# Pro_Co_RAT.net
KiCad netlist of a schematic drawn in Altium Designer
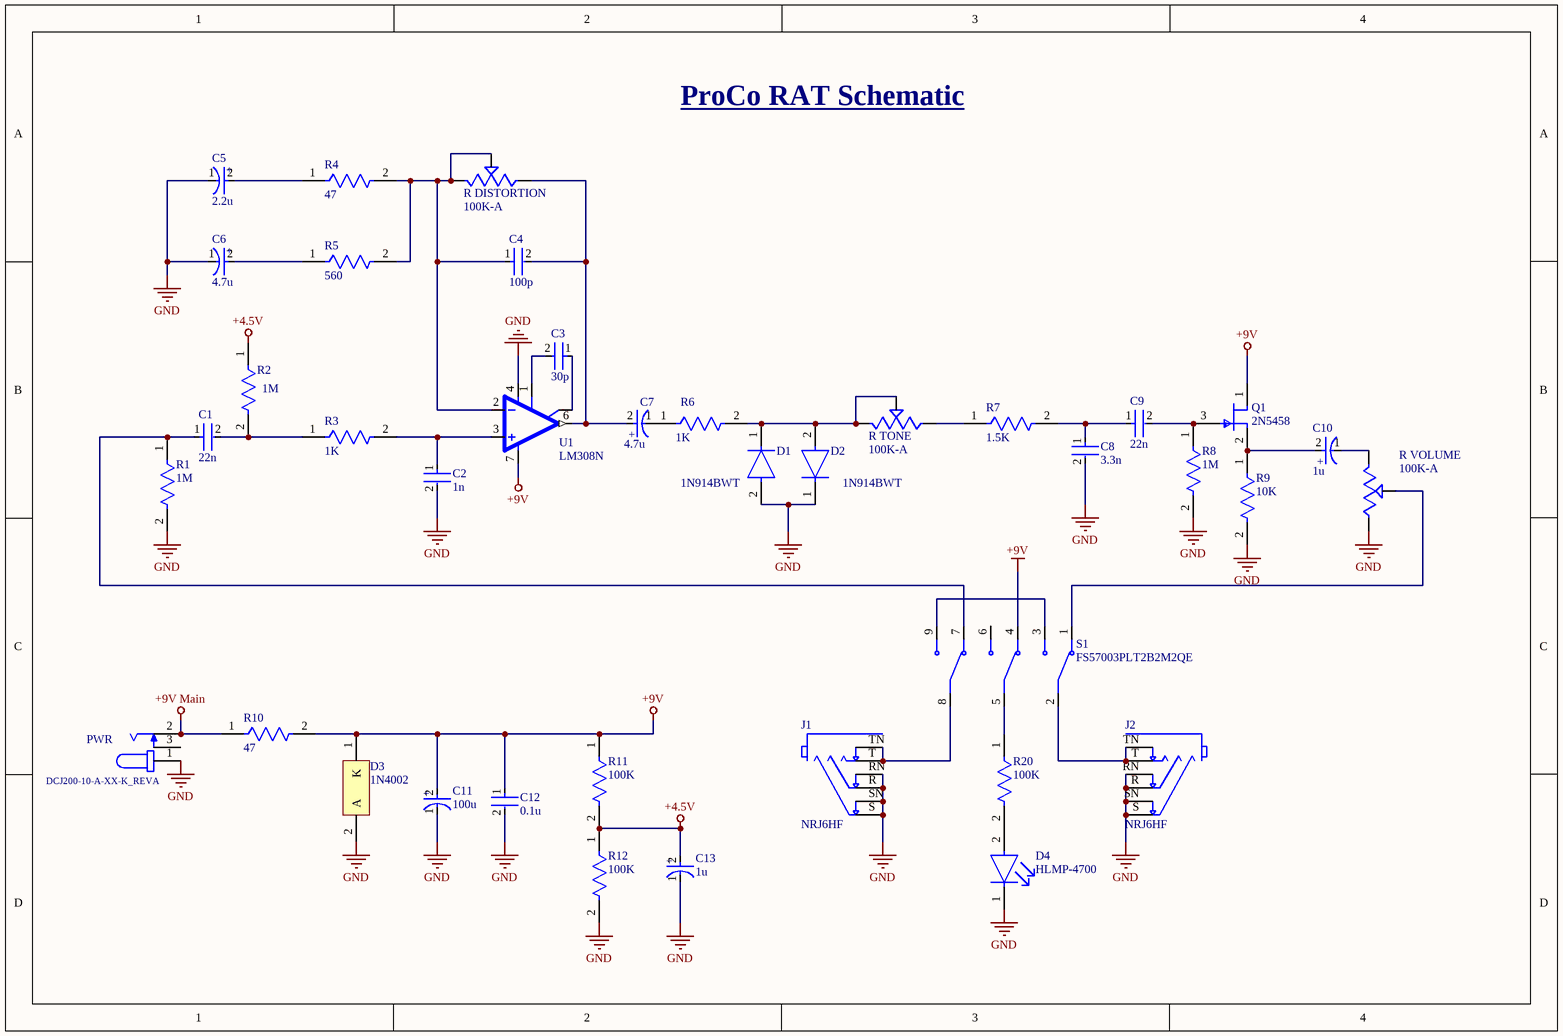
[diagram p0: Pro Co RAT.SchDoc]

(export (version "E")
  (design (tool "Eeschema 10.0.6"))
  (components
    (comp (ref "C1")
      (value "22n")
      (footprint "FP-VY2332M41Y5US63V7-MFG")
      (description "Capacitor Radiall")
      (fields (field (name "TOLERANCE") "20%"))
      (libsource (lib "Altium Content Vault") (part "11868f565c42a9108669ba33697ecf6"))
    )
    (comp (ref "C2")
      (value "1n")
      (footprint "FP-VY2332M41Y5US63V7-MFG")
      (description "Capacitor Radiall")
      (fields (field (name "TOLERANCE") "20%"))
      (libsource (lib "Altium Content Vault") (part "11868f565c42a9108669ba33697ecf6"))
    )
    (comp (ref "C3")
      (value "30p")
      (footprint "FP-VY2332M41Y5US63V7-MFG")
      (description "Capacitor Radiall")
      (fields (field (name "TOLERANCE") "20%"))
      (libsource (lib "Altium Content Vault") (part "11868f565c42a9108669ba33697ecf6"))
    )
    (comp (ref "C4")
      (value "100p")
      (footprint "FP-VY2332M41Y5US63V7-MFG")
      (description "Capacitor Radiall")
      (fields (field (name "TOLERANCE") "20%"))
      (libsource (lib "Altium Content Vault") (part "11868f565c42a9108669ba33697ecf6"))
    )
    (comp (ref "C5")
      (value "2.2u")
      (footprint "FP-RAD-TH-D_8_0_5-L_11_5-MFG")
      (description "Aluminum Electrolytic Capacitors (Radial Lead Type) 680uF ±20% 10V")
      (fields (field (name "TOLERANCE") "20%") (field (name "VOLTAGE") "10V"))
      (libsource (lib "Altium Content Vault") (part "a00bbbee19879c290e62620ae7e47b1"))
    )
    (comp (ref "C6")
      (value "4.7u")
      (footprint "FP-RAD-TH-D_8_0_5-L_11_5-MFG")
      (description "Aluminum Electrolytic Capacitors (Radial Lead Type) 680uF ±20% 10V")
      (fields (field (name "TOLERANCE") "20%") (field (name "VOLTAGE") "10V"))
      (libsource (lib "Altium Content Vault") (part "a00bbbee19879c290e62620ae7e47b1"))
    )
    (comp (ref "C7")
      (value "4.7u")
      (footprint "FP-RAD-TH-D_8_0_5-L_11_5-MFG")
      (description "Aluminum Electrolytic Capacitors (Radial Lead Type) 680uF ±20% 10V")
      (fields (field (name "TOLERANCE") "20%") (field (name "VOLTAGE") "10V"))
      (libsource (lib "Altium Content Vault") (part "a00bbbee19879c290e62620ae7e47b1"))
    )
    (comp (ref "C8")
      (value "3.3n")
      (footprint "FP-VY2332M41Y5US63V7-MFG")
      (description "Capacitor Radiall")
      (fields (field (name "TOLERANCE") "20%"))
      (libsource (lib "Altium Content Vault") (part "11868f565c42a9108669ba33697ecf6"))
    )
    (comp (ref "C9")
      (value "22n")
      (footprint "FP-VY2332M41Y5US63V7-MFG")
      (description "Capacitor Radiall")
      (fields (field (name "TOLERANCE") "20%"))
      (libsource (lib "Altium Content Vault") (part "11868f565c42a9108669ba33697ecf6"))
    )
    (comp (ref "C10")
      (value "1u")
      (footprint "FP-RAD-TH-D_8_0_5-L_11_5-MFG")
      (description "Aluminum Electrolytic Capacitors (Radial Lead Type) 680uF ±20% 10V")
      (fields (field (name "TOLERANCE") "20%") (field (name "VOLTAGE") "10V"))
      (libsource (lib "Altium Content Vault") (part "a00bbbee19879c290e62620ae7e47b1"))
    )
    (comp (ref "C11")
      (value "100u")
      (footprint "FP-RAD-TH-D_8_0_5-L_11_5-MFG")
      (description "Aluminum Electrolytic Capacitors (Radial Lead Type) 680uF ±20% 10V")
      (fields (field (name "TOLERANCE") "20%") (field (name "VOLTAGE") "10V"))
      (libsource (lib "Altium Content Vault") (part "a00bbbee19879c290e62620ae7e47b1"))
    )
    (comp (ref "C12")
      (value "0.1u")
      (footprint "FP-VY2332M41Y5US63V7-MFG")
      (description "Capacitor Radiall")
      (fields (field (name "TOLERANCE") "20%"))
      (libsource (lib "Altium Content Vault") (part "11868f565c42a9108669ba33697ecf6"))
    )
    (comp (ref "C13")
      (value "1u")
      (footprint "FP-RAD-TH-D_8_0_5-L_11_5-MFG")
      (description "Aluminum Electrolytic Capacitors (Radial Lead Type) 680uF ±20% 10V")
      (fields (field (name "TOLERANCE") "20%") (field (name "VOLTAGE") "10V"))
      (libsource (lib "Altium Content Vault") (part "a00bbbee19879c290e62620ae7e47b1"))
    )
    (comp (ref "D1")
      (value "1N914BWT")
      (footprint "FP-502-01-MFG")
      (description "DIODE GEN PURP 75V 200MA SOD523F")
      (fields
        (field (name "OCTOPART") "https://octopart.com/1n914bwt-on+semiconductor-84323166")
        (field (name "MANUFACTURER") "ON Semiconductor")
      )
      (libsource (lib "Altium Content Vault") (part "d7152d700b627762746794eb795d46e"))
    )
    (comp (ref "D2")
      (value "1N914BWT")
      (footprint "FP-502-01-MFG")
      (description "DIODE GEN PURP 75V 200MA SOD523F")
      (fields
        (field (name "OCTOPART") "https://octopart.com/1n914bwt-on+semiconductor-84323166")
        (field (name "MANUFACTURER") "ON Semiconductor")
      )
      (libsource (lib "Altium Content Vault") (part "d7152d700b627762746794eb795d46e"))
    )
    (comp (ref "D3")
      (value "1N4002")
      (footprint "ONSC-AXIAL_LEAD-2-59-10_P")
      (description "Standard Recovery Rectifier, 2-Pin Axial_Lead, Pb-Free, Bulk Bag")
      (fields (field (name "MANUFACTURER") "On Semiconductor"))
      (libsource (lib "Altium Content Vault") (part "ONSC-D-K1A2-2_A"))
    )
    (comp (ref "D4")
      (value "HLMP-4700")
      (footprint "FP-HLMP-4700-MFG")
      (description "LED RED DIFFUSED T-1 3/4 T/H")
      (fields
        (field (name "OCTOPART") "https://octopart.com/hlmp-4700-broadcom-71130526")
        (field (name "MANUFACTURER") "Broadcom")
      )
      (libsource (lib "Altium Content Vault") (part "8706943c75ba83719d021d2fdc84c58"))
    )
    (comp (ref "J1")
      (value "NRJ6HF")
      (footprint "NEUTRIK_NRJ6HF")
      (description "Jack Phone 1/4 in. Silver over Bronze cnts Horizontal PCB, Slim Jacks Series ¦ Neutrik NRJ6HF")
      (fields (field (name "MF") "Neutrik"))
      (libsource (lib "NRJ6HF") (part "NRJ6HF"))
    )
    (comp (ref "J2")
      (value "NRJ6HF")
      (footprint "NEUTRIK_NRJ6HF")
      (description "Jack Phone 1/4 in. Silver over Bronze cnts Horizontal PCB, Slim Jacks Series ¦ Neutrik NRJ6HF")
      (fields (field (name "MF") "Neutrik"))
      (libsource (lib "NRJ6HF") (part "NRJ6HF"))
    )
    (comp (ref "PWR")
      (value "DCJ200-10-A-XX-K_REVA")
      (footprint "GCT_DCJ200-10-A-XX-K_REVA")
      (description "Power Barrel Connector Jack 2.05mm ID (0.081), 5.50mm OD (0.217) Through Hole, Right Angle")
      (fields (field (name "MF") "Global Connector Technology") (field (name "MP") "DCJ200-10-A-K1-K"))
      (libsource (lib "DCJ200-10-A-XX-K_REVA") (part "DCJ200-10-A-XX-K_REVA"))
    )
    (comp (ref "Q1")
      (value "2N5458")
      (footprint "FP-29-11-MFG")
      (libsource (lib "Altium Content Vault") (part "2fe1325ee7984bd9864bb4197617735"))
    )
    (comp (ref "R DISTORTION")
      (value "100K-A")
      (footprint "POT_RD901F-40-15R1-B100K-00DL1")
      (description "Potentiometers 9mm Linear 100K Round Shaft")
      (fields (field (name "MF") "Alpha (Taiwan)") (field (name "MP") "RD901F-40-15R1-B100K-00DL1"))
      (libsource (lib "RD901F-40-15R1-B100K-00DL1") (part "RD901F-40-15R1-B100K-00DL1"))
    )
    (comp (ref "R TONE")
      (value "100K-A")
      (footprint "POT_RD901F-40-15R1-B100K-00DL1")
      (description "Potentiometers 9mm Linear 100K Round Shaft")
      (fields (field (name "MF") "Alpha (Taiwan)") (field (name "MP") "RD901F-40-15R1-B100K-00DL1"))
      (libsource (lib "RD901F-40-15R1-B100K-00DL1") (part "RD901F-40-15R1-B100K-00DL1"))
    )
    (comp (ref "R VOLUME")
      (value "100K-A")
      (footprint "POT_RD901F-40-15R1-B100K-00DL1")
      (description "Potentiometers 9mm Linear 100K Round Shaft")
      (fields (field (name "MF") "Alpha (Taiwan)") (field (name "MP") "RD901F-40-15R1-B100K-00DL1"))
      (libsource (lib "RD901F-40-15R1-B100K-00DL1") (part "RD901F-40-15R1-B100K-00DL1"))
    )
    (comp (ref "R1")
      (value "1M")
      (footprint "FP-MFR-25-MFG")
      (description "RES 1.18K OHM 1/4W 1% AXIAL")
      (fields (field (name "MANUFACTURER") "Yageo") (field (name "TOLERANCE") "1%"))
      (libsource (lib "Altium Content Vault") (part "1029c3af85768c4190bb7ad29bc67b5"))
    )
    (comp (ref "R2")
      (value "1M")
      (footprint "FP-MFR-25-MFG")
      (description "RES 1.18K OHM 1/4W 1% AXIAL")
      (fields (field (name "MANUFACTURER") "Yageo") (field (name "TOLERANCE") "1%"))
      (libsource (lib "Altium Content Vault") (part "1029c3af85768c4190bb7ad29bc67b5"))
    )
    (comp (ref "R3")
      (value "1K")
      (footprint "FP-MFR-25-MFG")
      (description "RES 1.18K OHM 1/4W 1% AXIAL")
      (fields (field (name "MANUFACTURER") "Yageo") (field (name "TOLERANCE") "1%"))
      (libsource (lib "Altium Content Vault") (part "1029c3af85768c4190bb7ad29bc67b5"))
    )
    (comp (ref "R4")
      (value "47")
      (footprint "FP-MFR-25-MFG")
      (description "RES 1.18K OHM 1/4W 1% AXIAL")
      (fields (field (name "MANUFACTURER") "Yageo") (field (name "TOLERANCE") "1%"))
      (libsource (lib "Altium Content Vault") (part "1029c3af85768c4190bb7ad29bc67b5"))
    )
    (comp (ref "R5")
      (value "560")
      (footprint "FP-MFR-25-MFG")
      (description "RES 1.18K OHM 1/4W 1% AXIAL")
      (fields (field (name "MANUFACTURER") "Yageo") (field (name "TOLERANCE") "1%"))
      (libsource (lib "Altium Content Vault") (part "1029c3af85768c4190bb7ad29bc67b5"))
    )
    (comp (ref "R6")
      (value "1K")
      (footprint "FP-MFR-25-MFG")
      (description "RES 1.18K OHM 1/4W 1% AXIAL")
      (fields (field (name "MANUFACTURER") "Yageo") (field (name "TOLERANCE") "1%"))
      (libsource (lib "Altium Content Vault") (part "1029c3af85768c4190bb7ad29bc67b5"))
    )
    (comp (ref "R7")
      (value "1.5K")
      (footprint "FP-MFR-25-MFG")
      (description "RES 1.18K OHM 1/4W 1% AXIAL")
      (fields (field (name "MANUFACTURER") "Yageo") (field (name "TOLERANCE") "1%"))
      (libsource (lib "Altium Content Vault") (part "1029c3af85768c4190bb7ad29bc67b5"))
    )
    (comp (ref "R8")
      (value "1M")
      (footprint "FP-MFR-25-MFG")
      (description "RES 1.18K OHM 1/4W 1% AXIAL")
      (fields (field (name "MANUFACTURER") "Yageo") (field (name "TOLERANCE") "1%"))
      (libsource (lib "Altium Content Vault") (part "1029c3af85768c4190bb7ad29bc67b5"))
    )
    (comp (ref "R9")
      (value "10K")
      (footprint "FP-MFR-25-MFG")
      (description "RES 1.18K OHM 1/4W 1% AXIAL")
      (fields (field (name "MANUFACTURER") "Yageo") (field (name "TOLERANCE") "1%"))
      (libsource (lib "Altium Content Vault") (part "1029c3af85768c4190bb7ad29bc67b5"))
    )
    (comp (ref "R10")
      (value "47")
      (footprint "FP-MFR-25-MFG")
      (description "RES 1.18K OHM 1/4W 1% AXIAL")
      (fields (field (name "MANUFACTURER") "Yageo") (field (name "TOLERANCE") "1%"))
      (libsource (lib "Altium Content Vault") (part "1029c3af85768c4190bb7ad29bc67b5"))
    )
    (comp (ref "R11")
      (value "100K")
      (footprint "FP-MFR-25-MFG")
      (description "RES 1.18K OHM 1/4W 1% AXIAL")
      (fields (field (name "MANUFACTURER") "Yageo") (field (name "TOLERANCE") "1%"))
      (libsource (lib "Altium Content Vault") (part "1029c3af85768c4190bb7ad29bc67b5"))
    )
    (comp (ref "R12")
      (value "100K")
      (footprint "FP-MFR-25-MFG")
      (description "RES 1.18K OHM 1/4W 1% AXIAL")
      (fields (field (name "MANUFACTURER") "Yageo") (field (name "TOLERANCE") "1%"))
      (libsource (lib "Altium Content Vault") (part "1029c3af85768c4190bb7ad29bc67b5"))
    )
    (comp (ref "R20")
      (value "100K")
      (footprint "FP-MFR-25-MFG")
      (description "RES 1.18K OHM 1/4W 1% AXIAL")
      (fields (field (name "MANUFACTURER") "Yageo") (field (name "TOLERANCE") "1%"))
      (libsource (lib "Altium Content Vault") (part "1029c3af85768c4190bb7ad29bc67b5"))
    )
    (comp (ref "S1")
      (value "FS57003PLT2B2M2QE")
      (footprint "SW_FS57003PLT2B2M2QE")
      (fields (field (name "MF") "E-Switch"))
      (libsource (lib "FS57003PLT2B2M2QE") (part "FS57003PLT2B2M2QE"))
    )
    (comp (ref "U1")
      (value "LM308N")
      (footprint "DIL08")
      (description "Ic 8-Pin Dip Op Amp Single Bipolar Ic 8-Pin Dip Op Amp Single Bipolar")
      (fields (field (name "MF") "MCM Electronics"))
      (libsource (lib "LM308N (1)") (part "LM308N"))
    )
  )
  (nets
    (net (code "1") (name "+4.5V") (class "Default")
      (node (ref "C13") (pin "2") (pinfunction "A_2") (pintype "passive"))
      (node (ref "R11") (pin "2") (pinfunction "2_2") (pintype "passive"))
      (node (ref "R12") (pin "1") (pinfunction "1_1") (pintype "passive"))
      (node (ref "R2") (pin "1") (pinfunction "1_1") (pintype "passive"))
    )
    (net (code "2") (name "+9V") (class "Default")
      (node (ref "C11") (pin "2") (pinfunction "A_2") (pintype "passive"))
      (node (ref "C12") (pin "1") (pinfunction "1_1") (pintype "passive"))
      (node (ref "D3") (pin "1") (pinfunction "K_1") (pintype "passive"))
      (node (ref "Q1") (pin "1") (pinfunction "DRAIN_1") (pintype "passive"))
      (node (ref "R10") (pin "2") (pinfunction "2_2") (pintype "passive"))
      (node (ref "R11") (pin "1") (pinfunction "1_1") (pintype "passive"))
      (node (ref "S1") (pin "4") (pinfunction "4_4") (pintype "passive"))
      (node (ref "U1") (pin "7") (pinfunction "V+_7") (pintype "power_in"))
    )
    (net (code "3") (name "+9V Main") (class "Default")
      (node (ref "PWR") (pin "2") (pinfunction "2_2") (pintype "passive"))
      (node (ref "R10") (pin "1") (pinfunction "1_1") (pintype "passive"))
    )
    (net (code "4") (name "GND") (class "Default")
      (node (ref "C11") (pin "1") (pinfunction "C_1") (pintype "passive"))
      (node (ref "C12") (pin "2") (pinfunction "2_2") (pintype "passive"))
      (node (ref "C13") (pin "1") (pinfunction "C_1") (pintype "passive"))
      (node (ref "C2") (pin "2") (pinfunction "2_2") (pintype "passive"))
      (node (ref "C5") (pin "1") (pinfunction "C_1") (pintype "passive"))
      (node (ref "C6") (pin "1") (pinfunction "C_1") (pintype "passive"))
      (node (ref "C8") (pin "2") (pinfunction "2_2") (pintype "passive"))
      (node (ref "D1") (pin "2") (pinfunction "A_2") (pintype "passive"))
      (node (ref "D2") (pin "1") (pinfunction "C_1") (pintype "passive"))
      (node (ref "D3") (pin "2") (pinfunction "A_2") (pintype "passive"))
      (node (ref "D4") (pin "1") (pinfunction "C_1") (pintype "passive"))
      (node (ref "J1") (pin "R") (pinfunction "R_R") (pintype "passive"))
      (node (ref "J1") (pin "RN") (pinfunction "RN_RN") (pintype "passive"))
      (node (ref "J1") (pin "S") (pinfunction "S_S") (pintype "passive"))
      (node (ref "J1") (pin "SN") (pinfunction "SN_SN") (pintype "passive"))
      (node (ref "J2") (pin "R") (pinfunction "R_R") (pintype "passive"))
      (node (ref "J2") (pin "RN") (pinfunction "RN_RN") (pintype "passive"))
      (node (ref "J2") (pin "S") (pinfunction "S_S") (pintype "passive"))
      (node (ref "J2") (pin "SN") (pinfunction "SN_SN") (pintype "passive"))
      (node (ref "PWR") (pin "1") (pinfunction "1_1") (pintype "passive"))
      (node (ref "R VOLUME") (pin "1") (pinfunction "1_1") (pintype "passive"))
      (node (ref "R1") (pin "2") (pinfunction "2_2") (pintype "passive"))
      (node (ref "R12") (pin "2") (pinfunction "2_2") (pintype "passive"))
      (node (ref "R8") (pin "2") (pinfunction "2_2") (pintype "passive"))
      (node (ref "R9") (pin "2") (pinfunction "2_2") (pintype "passive"))
      (node (ref "U1") (pin "4") (pinfunction "V-_4") (pintype "power_in"))
    )
    (net (code "5") (name "Net-(C1-Pad1)") (class "Default")
      (node (ref "C1") (pin "1") (pinfunction "1_1") (pintype "passive"))
      (node (ref "R1") (pin "1") (pinfunction "1_1") (pintype "passive"))
      (node (ref "S1") (pin "7") (pinfunction "7_7") (pintype "passive"))
    )
    (net (code "6") (name "Net-(C1-Pad2)") (class "Default")
      (node (ref "C1") (pin "2") (pinfunction "2_2") (pintype "passive"))
      (node (ref "R2") (pin "2") (pinfunction "2_2") (pintype "passive"))
      (node (ref "R3") (pin "1") (pinfunction "1_1") (pintype "passive"))
    )
    (net (code "7") (name "Net-(C5-A)") (class "Default")
      (node (ref "C5") (pin "2") (pinfunction "A_2") (pintype "passive"))
      (node (ref "R4") (pin "1") (pinfunction "1_1") (pintype "passive"))
    )
    (net (code "8") (name "Net-(C6-A)") (class "Default")
      (node (ref "C6") (pin "2") (pinfunction "A_2") (pintype "passive"))
      (node (ref "R5") (pin "1") (pinfunction "1_1") (pintype "passive"))
    )
    (net (code "9") (name "Net-(C7-A)") (class "Default")
      (node (ref "C4") (pin "2") (pinfunction "2_2") (pintype "passive"))
      (node (ref "C7") (pin "2") (pinfunction "A_2") (pintype "passive"))
      (node (ref "R DISTORTION") (pin "1") (pinfunction "1_1") (pintype "passive"))
      (node (ref "U1") (pin "6") (pinfunction "OUT_6") (pintype "output"))
    )
    (net (code "10") (name "Net-(C7-C)") (class "Default")
      (node (ref "C7") (pin "1") (pinfunction "C_1") (pintype "passive"))
      (node (ref "R6") (pin "1") (pinfunction "1_1") (pintype "passive"))
    )
    (net (code "11") (name "Net-(C8-Pad1)") (class "Default")
      (node (ref "C8") (pin "1") (pinfunction "1_1") (pintype "passive"))
      (node (ref "C9") (pin "1") (pinfunction "1_1") (pintype "passive"))
      (node (ref "R7") (pin "2") (pinfunction "2_2") (pintype "passive"))
    )
    (net (code "12") (name "Net-(C10-A)") (class "Default")
      (node (ref "C10") (pin "2") (pinfunction "A_2") (pintype "passive"))
      (node (ref "Q1") (pin "2") (pinfunction "SOURCE_2") (pintype "passive"))
      (node (ref "R9") (pin "1") (pinfunction "1_1") (pintype "passive"))
    )
    (net (code "13") (name "Net-(C10-C)") (class "Default")
      (node (ref "C10") (pin "1") (pinfunction "C_1") (pintype "passive"))
      (node (ref "R VOLUME") (pin "3") (pinfunction "3_3") (pintype "passive"))
    )
    (net (code "14") (name "Net-(D1-C)") (class "Default")
      (node (ref "D1") (pin "1") (pinfunction "C_1") (pintype "passive"))
      (node (ref "D2") (pin "2") (pinfunction "A_2") (pintype "passive"))
      (node (ref "R TONE") (pin "2") (pinfunction "2_2") (pintype "passive"))
      (node (ref "R TONE") (pin "3") (pinfunction "3_3") (pintype "passive"))
      (node (ref "R6") (pin "2") (pinfunction "2_2") (pintype "passive"))
    )
    (net (code "15") (name "Net-(D4-A)") (class "Default")
      (node (ref "D4") (pin "2") (pinfunction "A_2") (pintype "passive"))
      (node (ref "R20") (pin "2") (pinfunction "2_2") (pintype "passive"))
    )
    (net (code "16") (name "Net-(J1-PadT)") (class "Default")
      (node (ref "J1") (pin "T") (pinfunction "T_T") (pintype "passive"))
      (node (ref "J1") (pin "TN") (pinfunction "TN_TN") (pintype "passive"))
      (node (ref "S1") (pin "8") (pinfunction "8_8") (pintype "passive"))
    )
    (net (code "17") (name "Net-(J2-PadT)") (class "Default")
      (node (ref "J2") (pin "T") (pinfunction "T_T") (pintype "passive"))
      (node (ref "J2") (pin "TN") (pinfunction "TN_TN") (pintype "passive"))
      (node (ref "S1") (pin "2") (pinfunction "2_2") (pintype "passive"))
    )
    (net (code "18") (name "Net-(Q1-GATE)") (class "Default")
      (node (ref "C9") (pin "2") (pinfunction "2_2") (pintype "passive"))
      (node (ref "Q1") (pin "3") (pinfunction "GATE_3") (pintype "passive"))
      (node (ref "R8") (pin "1") (pinfunction "1_1") (pintype "passive"))
    )
    (net (code "19") (name "Net-(R TONE-Pad1)") (class "Default")
      (node (ref "R TONE") (pin "1") (pinfunction "1_1") (pintype "passive"))
      (node (ref "R7") (pin "1") (pinfunction "1_1") (pintype "passive"))
    )
    (net (code "20") (name "Net-(R VOLUME-Pad2)") (class "Default")
      (node (ref "R VOLUME") (pin "2") (pinfunction "2_2") (pintype "passive"))
      (node (ref "S1") (pin "1") (pinfunction "1_1") (pintype "passive"))
    )
    (net (code "21") (name "Net-(R20-Pad1)") (class "Default")
      (node (ref "R20") (pin "1") (pinfunction "1_1") (pintype "passive"))
      (node (ref "S1") (pin "5") (pinfunction "5_5") (pintype "passive"))
    )
    (net (code "22") (name "Net-(S1-Pad3)") (class "Default")
      (node (ref "S1") (pin "3") (pinfunction "3_3") (pintype "passive"))
      (node (ref "S1") (pin "9") (pinfunction "9_9") (pintype "passive"))
    )
    (net (code "23") (name "Net-(U1-+IN)") (class "Default")
      (node (ref "C2") (pin "1") (pinfunction "1_1") (pintype "passive"))
      (node (ref "R3") (pin "2") (pinfunction "2_2") (pintype "passive"))
      (node (ref "U1") (pin "3") (pinfunction "+IN_3") (pintype "passive"))
    )
    (net (code "24") (name "Net-(U1--IN)") (class "Default")
      (node (ref "C4") (pin "1") (pinfunction "1_1") (pintype "passive"))
      (node (ref "R DISTORTION") (pin "2") (pinfunction "2_2") (pintype "passive"))
      (node (ref "R DISTORTION") (pin "3") (pinfunction "3_3") (pintype "passive"))
      (node (ref "R4") (pin "2") (pinfunction "2_2") (pintype "passive"))
      (node (ref "R5") (pin "2") (pinfunction "2_2") (pintype "passive"))
      (node (ref "U1") (pin "2") (pinfunction "-IN_2") (pintype "passive"))
    )
    (net (code "25") (name "Net-(U1-CMP1)") (class "Default")
      (node (ref "C3") (pin "2") (pinfunction "2_2") (pintype "passive"))
      (node (ref "U1") (pin "1") (pinfunction "CMP1_1") (pintype "passive"))
    )
    (net (code "26") (name "Net-(U1-CMP2)") (class "Default")
      (node (ref "C3") (pin "1") (pinfunction "1_1") (pintype "passive"))
      (node (ref "U1") (pin "8") (pinfunction "CMP2_8") (pintype "passive"))
    )
    (net (code "27") (name "unconnected-(PWR-Pad3)") (class "Default")
      (node (ref "PWR") (pin "3") (pinfunction "3_3") (pintype "passive"))
    )
    (net (code "28") (name "unconnected-(S1-Pad6)") (class "Default")
      (node (ref "S1") (pin "6") (pinfunction "6_6") (pintype "passive"))
    )
  )
)
